# sdl_adapter.net
KiCad netlist of a schematic drawn in Altium Designer
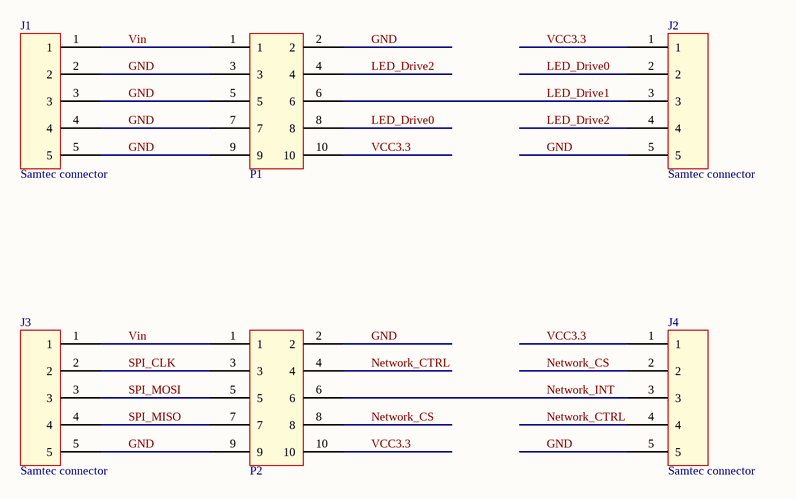
[diagram p0: sdl_adapter.SchDoc]

(export (version "E")
  (design (tool "Eeschema 10.0.6"))
  (components
    (comp (ref "J1")
      (value "Samtec connector")
      (footprint "TFM-105-02-L-S")
      (description "Samtec connector, 1.27 mm, single row, 5 pos SMD")
      (libsource (lib "") (part "Samtec conntector_1"))
    )
    (comp (ref "J2")
      (value "Samtec connector")
      (footprint "TFM-105-02-L-S")
      (description "Samtec connector, 1.27 mm, single row, 5 pos SMD")
      (libsource (lib "connectors") (part "Samtec conntector"))
    )
    (comp (ref "J3")
      (value "Samtec connector")
      (footprint "TFM-105-02-L-S")
      (description "Samtec connector, 1.27 mm, single row, 5 pos SMD")
      (libsource (lib "") (part "Samtec conntector_1"))
    )
    (comp (ref "J4")
      (value "Samtec connector")
      (footprint "TFM-105-02-L-S")
      (description "Samtec connector, 1.27 mm, single row, 5 pos SMD")
      (libsource (lib "connectors") (part "Samtec conntector"))
    )
    (comp (ref "P1")
      (value "2 x 5 header SMD")
      (footprint "2x5 header SMD")
      (description "2x5 100 mil header SMD")
      (libsource (lib "connectors") (part "2 x 5 header SMD"))
    )
    (comp (ref "P2")
      (value "2 x 5 header SMD")
      (footprint "2x5 header SMD")
      (description "2x5 100 mil header SMD")
      (libsource (lib "connectors") (part "2 x 5 header SMD"))
    )
  )
  (nets
    (net (code "1") (name "/GND") (class "Default")
      (node (ref "J1") (pin "2") (pinfunction "2_2") (pintype "passive"))
      (node (ref "J1") (pin "3") (pinfunction "3_3") (pintype "passive"))
      (node (ref "J1") (pin "4") (pinfunction "4_4") (pintype "passive"))
      (node (ref "J1") (pin "5") (pinfunction "5_5") (pintype "passive"))
      (node (ref "J2") (pin "5") (pinfunction "5_5") (pintype "passive"))
      (node (ref "J3") (pin "5") (pinfunction "5_5") (pintype "passive"))
      (node (ref "J4") (pin "5") (pinfunction "5_5") (pintype "passive"))
      (node (ref "P1") (pin "2") (pinfunction "2_2") (pintype "passive"))
      (node (ref "P1") (pin "3") (pinfunction "3_3") (pintype "passive"))
      (node (ref "P1") (pin "5") (pinfunction "5_5") (pintype "passive"))
      (node (ref "P1") (pin "7") (pinfunction "7_7") (pintype "passive"))
      (node (ref "P1") (pin "9") (pinfunction "9_9") (pintype "passive"))
      (node (ref "P2") (pin "2") (pinfunction "2_2") (pintype "passive"))
      (node (ref "P2") (pin "9") (pinfunction "9_9") (pintype "passive"))
    )
    (net (code "2") (name "/LED_Drive0") (class "Default")
      (node (ref "J2") (pin "2") (pinfunction "2_2") (pintype "passive"))
      (node (ref "P1") (pin "8") (pinfunction "8_8") (pintype "passive"))
    )
    (net (code "3") (name "/LED_Drive1") (class "Default")
      (node (ref "J2") (pin "3") (pinfunction "3_3") (pintype "passive"))
      (node (ref "P1") (pin "6") (pinfunction "6_6") (pintype "passive"))
    )
    (net (code "4") (name "/LED_Drive2") (class "Default")
      (node (ref "J2") (pin "4") (pinfunction "4_4") (pintype "passive"))
      (node (ref "P1") (pin "4") (pinfunction "4_4") (pintype "passive"))
    )
    (net (code "5") (name "/Network_CS") (class "Default")
      (node (ref "J4") (pin "2") (pinfunction "2_2") (pintype "passive"))
      (node (ref "P2") (pin "8") (pinfunction "8_8") (pintype "passive"))
    )
    (net (code "6") (name "/Network_CTRL") (class "Default")
      (node (ref "J4") (pin "4") (pinfunction "4_4") (pintype "passive"))
      (node (ref "P2") (pin "4") (pinfunction "4_4") (pintype "passive"))
    )
    (net (code "7") (name "/Network_INT") (class "Default")
      (node (ref "J4") (pin "3") (pinfunction "3_3") (pintype "passive"))
      (node (ref "P2") (pin "6") (pinfunction "6_6") (pintype "passive"))
    )
    (net (code "8") (name "/SPI_CLK") (class "Default")
      (node (ref "J3") (pin "2") (pinfunction "2_2") (pintype "passive"))
      (node (ref "P2") (pin "3") (pinfunction "3_3") (pintype "passive"))
    )
    (net (code "9") (name "/SPI_MISO") (class "Default")
      (node (ref "J3") (pin "4") (pinfunction "4_4") (pintype "passive"))
      (node (ref "P2") (pin "7") (pinfunction "7_7") (pintype "passive"))
    )
    (net (code "10") (name "/SPI_MOSI") (class "Default")
      (node (ref "J3") (pin "3") (pinfunction "3_3") (pintype "passive"))
      (node (ref "P2") (pin "5") (pinfunction "5_5") (pintype "passive"))
    )
    (net (code "11") (name "/VCC3.3") (class "Default")
      (node (ref "J2") (pin "1") (pinfunction "1_1") (pintype "passive"))
      (node (ref "J4") (pin "1") (pinfunction "1_1") (pintype "passive"))
      (node (ref "P1") (pin "10") (pinfunction "10_10") (pintype "passive"))
      (node (ref "P2") (pin "10") (pinfunction "10_10") (pintype "passive"))
    )
    (net (code "12") (name "/Vin") (class "Default")
      (node (ref "J1") (pin "1") (pinfunction "1_1") (pintype "passive"))
      (node (ref "J3") (pin "1") (pinfunction "1_1") (pintype "passive"))
      (node (ref "P1") (pin "1") (pinfunction "1_1") (pintype "passive"))
      (node (ref "P2") (pin "1") (pinfunction "1_1") (pintype "passive"))
    )
  )
)
